# stm32-discovery.net
KiCad netlist of a schematic drawn in EAGLE
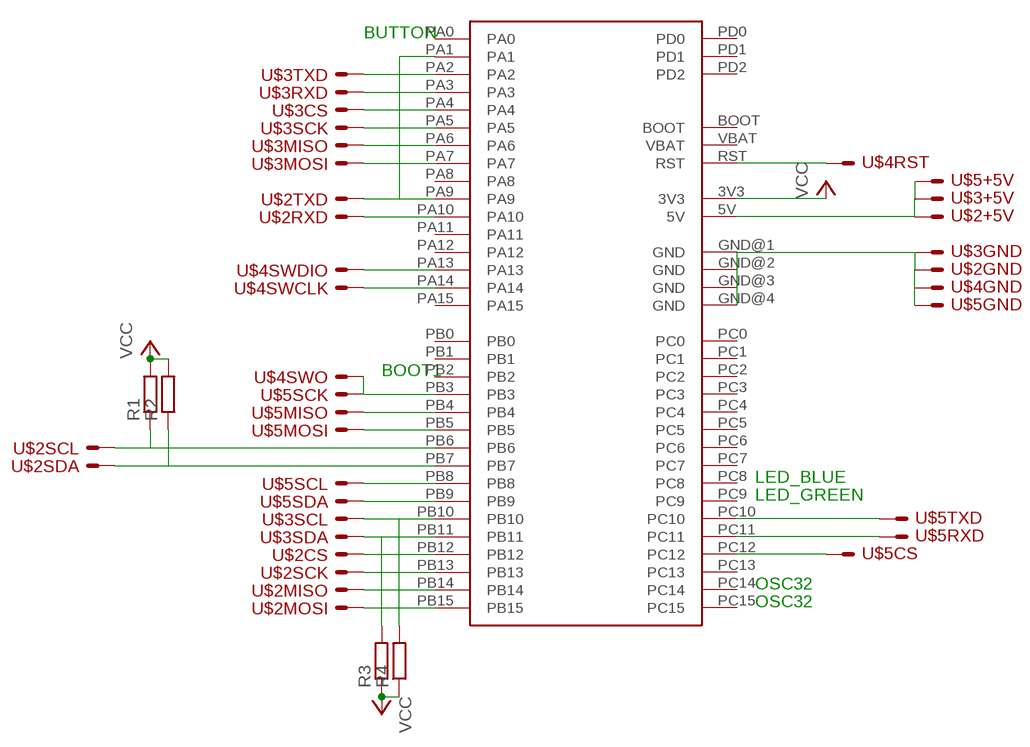
[diagram p0: schematic, sheet 1]

(export (version "E")
  (design (tool "Eeschema 10.0.6"))
  (components
    (comp (ref "R1")
      (value "R-EU_0204/7")
      (footprint "eagle-import:0204_7")
      (libsource (lib "eagle-import") (part "R-EU_0204/7"))
    )
    (comp (ref "R2")
      (value "R-EU_0204/7")
      (footprint "eagle-import:0204_7")
      (libsource (lib "eagle-import") (part "R-EU_0204/7"))
    )
    (comp (ref "R3")
      (value "R-EU_0204/7")
      (footprint "eagle-import:0204_7")
      (libsource (lib "eagle-import") (part "R-EU_0204/7"))
    )
    (comp (ref "R4")
      (value "R-EU_0204/7")
      (footprint "eagle-import:0204_7")
      (libsource (lib "eagle-import") (part "R-EU_0204/7"))
    )
    (comp (ref "U$1")
      (value "STM32_DISCOVERY")
      (footprint "eagle-import:STM32_DISCOVERY")
      (libsource (lib "eagle-import") (part "STM32_DISCOVERY"))
    )
    (comp (ref "U$2")
      (value "SPI_BUS")
      (footprint "eagle-import:SPI_BUS")
      (libsource (lib "eagle-import") (part "SPI_BUS"))
    )
    (comp (ref "U$3")
      (value "SPI_BUS")
      (footprint "eagle-import:SPI_BUS")
      (libsource (lib "eagle-import") (part "SPI_BUS"))
    )
    (comp (ref "U$4")
      (value "SWD")
      (footprint "eagle-import:SWD")
      (libsource (lib "eagle-import") (part "SWD"))
    )
    (comp (ref "U$5")
      (value "SPI_BUS")
      (footprint "eagle-import:SPI_BUS")
      (libsource (lib "eagle-import") (part "SPI_BUS"))
    )
  )
  (nets
    (net (code "1") (name "Net-(U$2A-S)") (class "Default")
      (node (ref "U$1") (pin "5V") (pinfunction "5V_5V") (pintype "bidirectional"))
      (node (ref "U$2") (pin "+5V") (pinfunction "S_+5V") (pintype "passive"))
      (node (ref "U$3") (pin "+5V") (pinfunction "S_+5V") (pintype "passive"))
      (node (ref "U$5") (pin "+5V") (pinfunction "S_+5V") (pintype "passive"))
    )
    (net (code "2") (name "Net-(U$2B-S)") (class "Default")
      (node (ref "U$1") (pin "PB12") (pinfunction "PB12_PB12") (pintype "bidirectional"))
      (node (ref "U$2") (pin "CS") (pinfunction "S_CS") (pintype "passive"))
    )
    (net (code "3") (name "Net-(U$2C-S)") (class "Default")
      (node (ref "U$1") (pin "GND@1") (pinfunction "GND_GND@1") (pintype "bidirectional"))
      (node (ref "U$1") (pin "GND@2") (pinfunction "GND_GND@2") (pintype "bidirectional"))
      (node (ref "U$1") (pin "GND@3") (pinfunction "GND_GND@3") (pintype "bidirectional"))
      (node (ref "U$1") (pin "GND@4") (pinfunction "GND_GND@4") (pintype "bidirectional"))
      (node (ref "U$2") (pin "GND") (pinfunction "S_GND") (pintype "passive"))
      (node (ref "U$3") (pin "GND") (pinfunction "S_GND") (pintype "passive"))
      (node (ref "U$4") (pin "GND") (pinfunction "S_GND") (pintype "passive"))
      (node (ref "U$5") (pin "GND") (pinfunction "S_GND") (pintype "passive"))
    )
    (net (code "4") (name "Net-(U$2D-S)") (class "Default")
      (node (ref "U$1") (pin "PB14") (pinfunction "PB14_PB14") (pintype "bidirectional"))
      (node (ref "U$2") (pin "MISO") (pinfunction "S_MISO") (pintype "passive"))
    )
    (net (code "5") (name "Net-(U$2E-S)") (class "Default")
      (node (ref "U$1") (pin "PB15") (pinfunction "PB15_PB15") (pintype "bidirectional"))
      (node (ref "U$2") (pin "MOSI") (pinfunction "S_MOSI") (pintype "passive"))
    )
    (net (code "6") (name "Net-(U$2F-S)") (class "Default")
      (node (ref "U$1") (pin "PA10") (pinfunction "PA10_PA10") (pintype "bidirectional"))
      (node (ref "U$2") (pin "RXD") (pinfunction "S_RXD") (pintype "passive"))
    )
    (net (code "7") (name "Net-(U$2G-S)") (class "Default")
      (node (ref "U$1") (pin "PB13") (pinfunction "PB13_PB13") (pintype "bidirectional"))
      (node (ref "U$2") (pin "SCK") (pinfunction "S_SCK") (pintype "passive"))
    )
    (net (code "8") (name "Net-(U$2H-S)") (class "Default")
      (node (ref "R1") (pin "1") (pinfunction "1_1") (pintype "passive"))
      (node (ref "U$1") (pin "PB6") (pinfunction "PB6_PB6") (pintype "bidirectional"))
      (node (ref "U$2") (pin "SCL") (pinfunction "S_SCL") (pintype "passive"))
    )
    (net (code "9") (name "Net-(U$2I-S)") (class "Default")
      (node (ref "R2") (pin "1") (pinfunction "1_1") (pintype "passive"))
      (node (ref "U$1") (pin "PB7") (pinfunction "PB7_PB7") (pintype "bidirectional"))
      (node (ref "U$2") (pin "SDA") (pinfunction "S_SDA") (pintype "passive"))
    )
    (net (code "10") (name "Net-(U$2J-S)") (class "Default")
      (node (ref "U$1") (pin "PA1") (pinfunction "PA1_PA1") (pintype "bidirectional"))
      (node (ref "U$1") (pin "PA9") (pinfunction "PA9_PA9") (pintype "bidirectional"))
      (node (ref "U$2") (pin "TXD") (pinfunction "S_TXD") (pintype "passive"))
    )
    (net (code "11") (name "Net-(U$3B-S)") (class "Default")
      (node (ref "U$1") (pin "PA4") (pinfunction "PA4_PA4") (pintype "bidirectional"))
      (node (ref "U$3") (pin "CS") (pinfunction "S_CS") (pintype "passive"))
    )
    (net (code "12") (name "Net-(U$3D-S)") (class "Default")
      (node (ref "U$1") (pin "PA6") (pinfunction "PA6_PA6") (pintype "bidirectional"))
      (node (ref "U$3") (pin "MISO") (pinfunction "S_MISO") (pintype "passive"))
    )
    (net (code "13") (name "Net-(U$3E-S)") (class "Default")
      (node (ref "U$1") (pin "PA7") (pinfunction "PA7_PA7") (pintype "bidirectional"))
      (node (ref "U$3") (pin "MOSI") (pinfunction "S_MOSI") (pintype "passive"))
    )
    (net (code "14") (name "Net-(U$3F-S)") (class "Default")
      (node (ref "U$1") (pin "PA3") (pinfunction "PA3_PA3") (pintype "bidirectional"))
      (node (ref "U$3") (pin "RXD") (pinfunction "S_RXD") (pintype "passive"))
    )
    (net (code "15") (name "Net-(U$3G-S)") (class "Default")
      (node (ref "U$1") (pin "PA5") (pinfunction "PA5_PA5") (pintype "bidirectional"))
      (node (ref "U$3") (pin "SCK") (pinfunction "S_SCK") (pintype "passive"))
    )
    (net (code "16") (name "Net-(U$3H-S)") (class "Default")
      (node (ref "R4") (pin "2") (pinfunction "2_2") (pintype "passive"))
      (node (ref "U$1") (pin "PB10") (pinfunction "PB10_PB10") (pintype "bidirectional"))
      (node (ref "U$3") (pin "SCL") (pinfunction "S_SCL") (pintype "passive"))
    )
    (net (code "17") (name "Net-(U$3I-S)") (class "Default")
      (node (ref "R3") (pin "2") (pinfunction "2_2") (pintype "passive"))
      (node (ref "U$1") (pin "PB11") (pinfunction "PB11_PB11") (pintype "bidirectional"))
      (node (ref "U$3") (pin "SDA") (pinfunction "S_SDA") (pintype "passive"))
    )
    (net (code "18") (name "Net-(U$3J-S)") (class "Default")
      (node (ref "U$1") (pin "PA2") (pinfunction "PA2_PA2") (pintype "bidirectional"))
      (node (ref "U$3") (pin "TXD") (pinfunction "S_TXD") (pintype "passive"))
    )
    (net (code "19") (name "Net-(U$4B-S)") (class "Default")
      (node (ref "U$1") (pin "RST") (pinfunction "RST_RST") (pintype "bidirectional"))
      (node (ref "U$4") (pin "RST") (pinfunction "S_RST") (pintype "passive"))
    )
    (net (code "20") (name "Net-(U$4C-S)") (class "Default")
      (node (ref "U$1") (pin "PA14") (pinfunction "PA14_PA14") (pintype "bidirectional"))
      (node (ref "U$4") (pin "SWCLK") (pinfunction "S_SWCLK") (pintype "passive"))
    )
    (net (code "21") (name "Net-(U$4D-S)") (class "Default")
      (node (ref "U$1") (pin "PA13") (pinfunction "PA13_PA13") (pintype "bidirectional"))
      (node (ref "U$4") (pin "SWDIO") (pinfunction "S_SWDIO") (pintype "passive"))
    )
    (net (code "22") (name "Net-(U$4E-S)") (class "Default")
      (node (ref "U$1") (pin "PB3") (pinfunction "PB3_PB3") (pintype "bidirectional"))
      (node (ref "U$4") (pin "SWO") (pinfunction "S_SWO") (pintype "passive"))
      (node (ref "U$5") (pin "SCK") (pinfunction "S_SCK") (pintype "passive"))
    )
    (net (code "23") (name "Net-(U$5B-S)") (class "Default")
      (node (ref "U$1") (pin "PC12") (pinfunction "PC12_PC12") (pintype "bidirectional"))
      (node (ref "U$5") (pin "CS") (pinfunction "S_CS") (pintype "passive"))
    )
    (net (code "24") (name "Net-(U$5D-S)") (class "Default")
      (node (ref "U$1") (pin "PB4") (pinfunction "PB4_PB4") (pintype "bidirectional"))
      (node (ref "U$5") (pin "MISO") (pinfunction "S_MISO") (pintype "passive"))
    )
    (net (code "25") (name "Net-(U$5E-S)") (class "Default")
      (node (ref "U$1") (pin "PB5") (pinfunction "PB5_PB5") (pintype "bidirectional"))
      (node (ref "U$5") (pin "MOSI") (pinfunction "S_MOSI") (pintype "passive"))
    )
    (net (code "26") (name "Net-(U$5F-S)") (class "Default")
      (node (ref "U$1") (pin "PC11") (pinfunction "PC11_PC11") (pintype "bidirectional"))
      (node (ref "U$5") (pin "RXD") (pinfunction "S_RXD") (pintype "passive"))
    )
    (net (code "27") (name "Net-(U$5H-S)") (class "Default")
      (node (ref "U$1") (pin "PB8") (pinfunction "PB8_PB8") (pintype "bidirectional"))
      (node (ref "U$5") (pin "SCL") (pinfunction "S_SCL") (pintype "passive"))
    )
    (net (code "28") (name "Net-(U$5I-S)") (class "Default")
      (node (ref "U$1") (pin "PB9") (pinfunction "PB9_PB9") (pintype "bidirectional"))
      (node (ref "U$5") (pin "SDA") (pinfunction "S_SDA") (pintype "passive"))
    )
    (net (code "29") (name "Net-(U$5J-S)") (class "Default")
      (node (ref "U$1") (pin "PC10") (pinfunction "PC10_PC10") (pintype "bidirectional"))
      (node (ref "U$5") (pin "TXD") (pinfunction "S_TXD") (pintype "passive"))
    )
    (net (code "30") (name "VCC") (class "Default")
      (node (ref "R1") (pin "2") (pinfunction "2_2") (pintype "passive"))
      (node (ref "R2") (pin "2") (pinfunction "2_2") (pintype "passive"))
      (node (ref "R3") (pin "1") (pinfunction "1_1") (pintype "passive"))
      (node (ref "R4") (pin "1") (pinfunction "1_1") (pintype "passive"))
      (node (ref "U$1") (pin "3V3") (pinfunction "3V3_3V3") (pintype "bidirectional"))
    )
    (net (code "31") (name "unconnected-(U$1-NC-PadNC@1)") (class "Default")
      (node (ref "U$1") (pin "NC@1") (pinfunction "NC_NC@1") (pintype "bidirectional"))
    )
    (net (code "32") (name "unconnected-(U$1-NC-PadNC@2)") (class "Default")
      (node (ref "U$1") (pin "NC@2") (pinfunction "NC_NC@2") (pintype "bidirectional"))
    )
    (net (code "33") (name "unconnected-(U$1-PadBOOT)") (class "Default")
      (node (ref "U$1") (pin "BOOT") (pinfunction "BOOT_BOOT") (pintype "bidirectional"))
    )
    (net (code "34") (name "unconnected-(U$1-PadPA0)") (class "Default")
      (node (ref "U$1") (pin "PA0") (pinfunction "PA0_PA0") (pintype "bidirectional"))
    )
    (net (code "35") (name "unconnected-(U$1-PadPA8)") (class "Default")
      (node (ref "U$1") (pin "PA8") (pinfunction "PA8_PA8") (pintype "bidirectional"))
    )
    (net (code "36") (name "unconnected-(U$1-PadPA11)") (class "Default")
      (node (ref "U$1") (pin "PA11") (pinfunction "PA11_PA11") (pintype "bidirectional"))
    )
    (net (code "37") (name "unconnected-(U$1-PadPA12)") (class "Default")
      (node (ref "U$1") (pin "PA12") (pinfunction "PA12_PA12") (pintype "bidirectional"))
    )
    (net (code "38") (name "unconnected-(U$1-PadPA15)") (class "Default")
      (node (ref "U$1") (pin "PA15") (pinfunction "PA15_PA15") (pintype "bidirectional"))
    )
    (net (code "39") (name "unconnected-(U$1-PadPB0)") (class "Default")
      (node (ref "U$1") (pin "PB0") (pinfunction "PB0_PB0") (pintype "bidirectional"))
    )
    (net (code "40") (name "unconnected-(U$1-PadPB1)") (class "Default")
      (node (ref "U$1") (pin "PB1") (pinfunction "PB1_PB1") (pintype "bidirectional"))
    )
    (net (code "41") (name "unconnected-(U$1-PadPB2)") (class "Default")
      (node (ref "U$1") (pin "PB2") (pinfunction "PB2_PB2") (pintype "bidirectional"))
    )
    (net (code "42") (name "unconnected-(U$1-PadPC0)") (class "Default")
      (node (ref "U$1") (pin "PC0") (pinfunction "PC0_PC0") (pintype "bidirectional"))
    )
    (net (code "43") (name "unconnected-(U$1-PadPC1)") (class "Default")
      (node (ref "U$1") (pin "PC1") (pinfunction "PC1_PC1") (pintype "bidirectional"))
    )
    (net (code "44") (name "unconnected-(U$1-PadPC2)") (class "Default")
      (node (ref "U$1") (pin "PC2") (pinfunction "PC2_PC2") (pintype "bidirectional"))
    )
    (net (code "45") (name "unconnected-(U$1-PadPC3)") (class "Default")
      (node (ref "U$1") (pin "PC3") (pinfunction "PC3_PC3") (pintype "bidirectional"))
    )
    (net (code "46") (name "unconnected-(U$1-PadPC4)") (class "Default")
      (node (ref "U$1") (pin "PC4") (pinfunction "PC4_PC4") (pintype "bidirectional"))
    )
    (net (code "47") (name "unconnected-(U$1-PadPC5)") (class "Default")
      (node (ref "U$1") (pin "PC5") (pinfunction "PC5_PC5") (pintype "bidirectional"))
    )
    (net (code "48") (name "unconnected-(U$1-PadPC6)") (class "Default")
      (node (ref "U$1") (pin "PC6") (pinfunction "PC6_PC6") (pintype "bidirectional"))
    )
    (net (code "49") (name "unconnected-(U$1-PadPC7)") (class "Default")
      (node (ref "U$1") (pin "PC7") (pinfunction "PC7_PC7") (pintype "bidirectional"))
    )
    (net (code "50") (name "unconnected-(U$1-PadPC8)") (class "Default")
      (node (ref "U$1") (pin "PC8") (pinfunction "PC8_PC8") (pintype "bidirectional"))
    )
    (net (code "51") (name "unconnected-(U$1-PadPC9)") (class "Default")
      (node (ref "U$1") (pin "PC9") (pinfunction "PC9_PC9") (pintype "bidirectional"))
    )
    (net (code "52") (name "unconnected-(U$1-PadPC13)") (class "Default")
      (node (ref "U$1") (pin "PC13") (pinfunction "PC13_PC13") (pintype "bidirectional"))
    )
    (net (code "53") (name "unconnected-(U$1-PadPC14)") (class "Default")
      (node (ref "U$1") (pin "PC14") (pinfunction "PC14_PC14") (pintype "bidirectional"))
    )
    (net (code "54") (name "unconnected-(U$1-PadPC15)") (class "Default")
      (node (ref "U$1") (pin "PC15") (pinfunction "PC15_PC15") (pintype "bidirectional"))
    )
    (net (code "55") (name "unconnected-(U$1-PadPD0)") (class "Default")
      (node (ref "U$1") (pin "PD0") (pinfunction "PD0_PD0") (pintype "bidirectional"))
    )
    (net (code "56") (name "unconnected-(U$1-PadPD1)") (class "Default")
      (node (ref "U$1") (pin "PD1") (pinfunction "PD1_PD1") (pintype "bidirectional"))
    )
    (net (code "57") (name "unconnected-(U$1-PadPD2)") (class "Default")
      (node (ref "U$1") (pin "PD2") (pinfunction "PD2_PD2") (pintype "bidirectional"))
    )
    (net (code "58") (name "unconnected-(U$1-PadVBAT)") (class "Default")
      (node (ref "U$1") (pin "VBAT") (pinfunction "VBAT_VBAT") (pintype "bidirectional"))
    )
  )
)
